# 12_BCKPLN_FPGA_J008340B.net
KiCad netlist of a schematic drawn in EAGLE
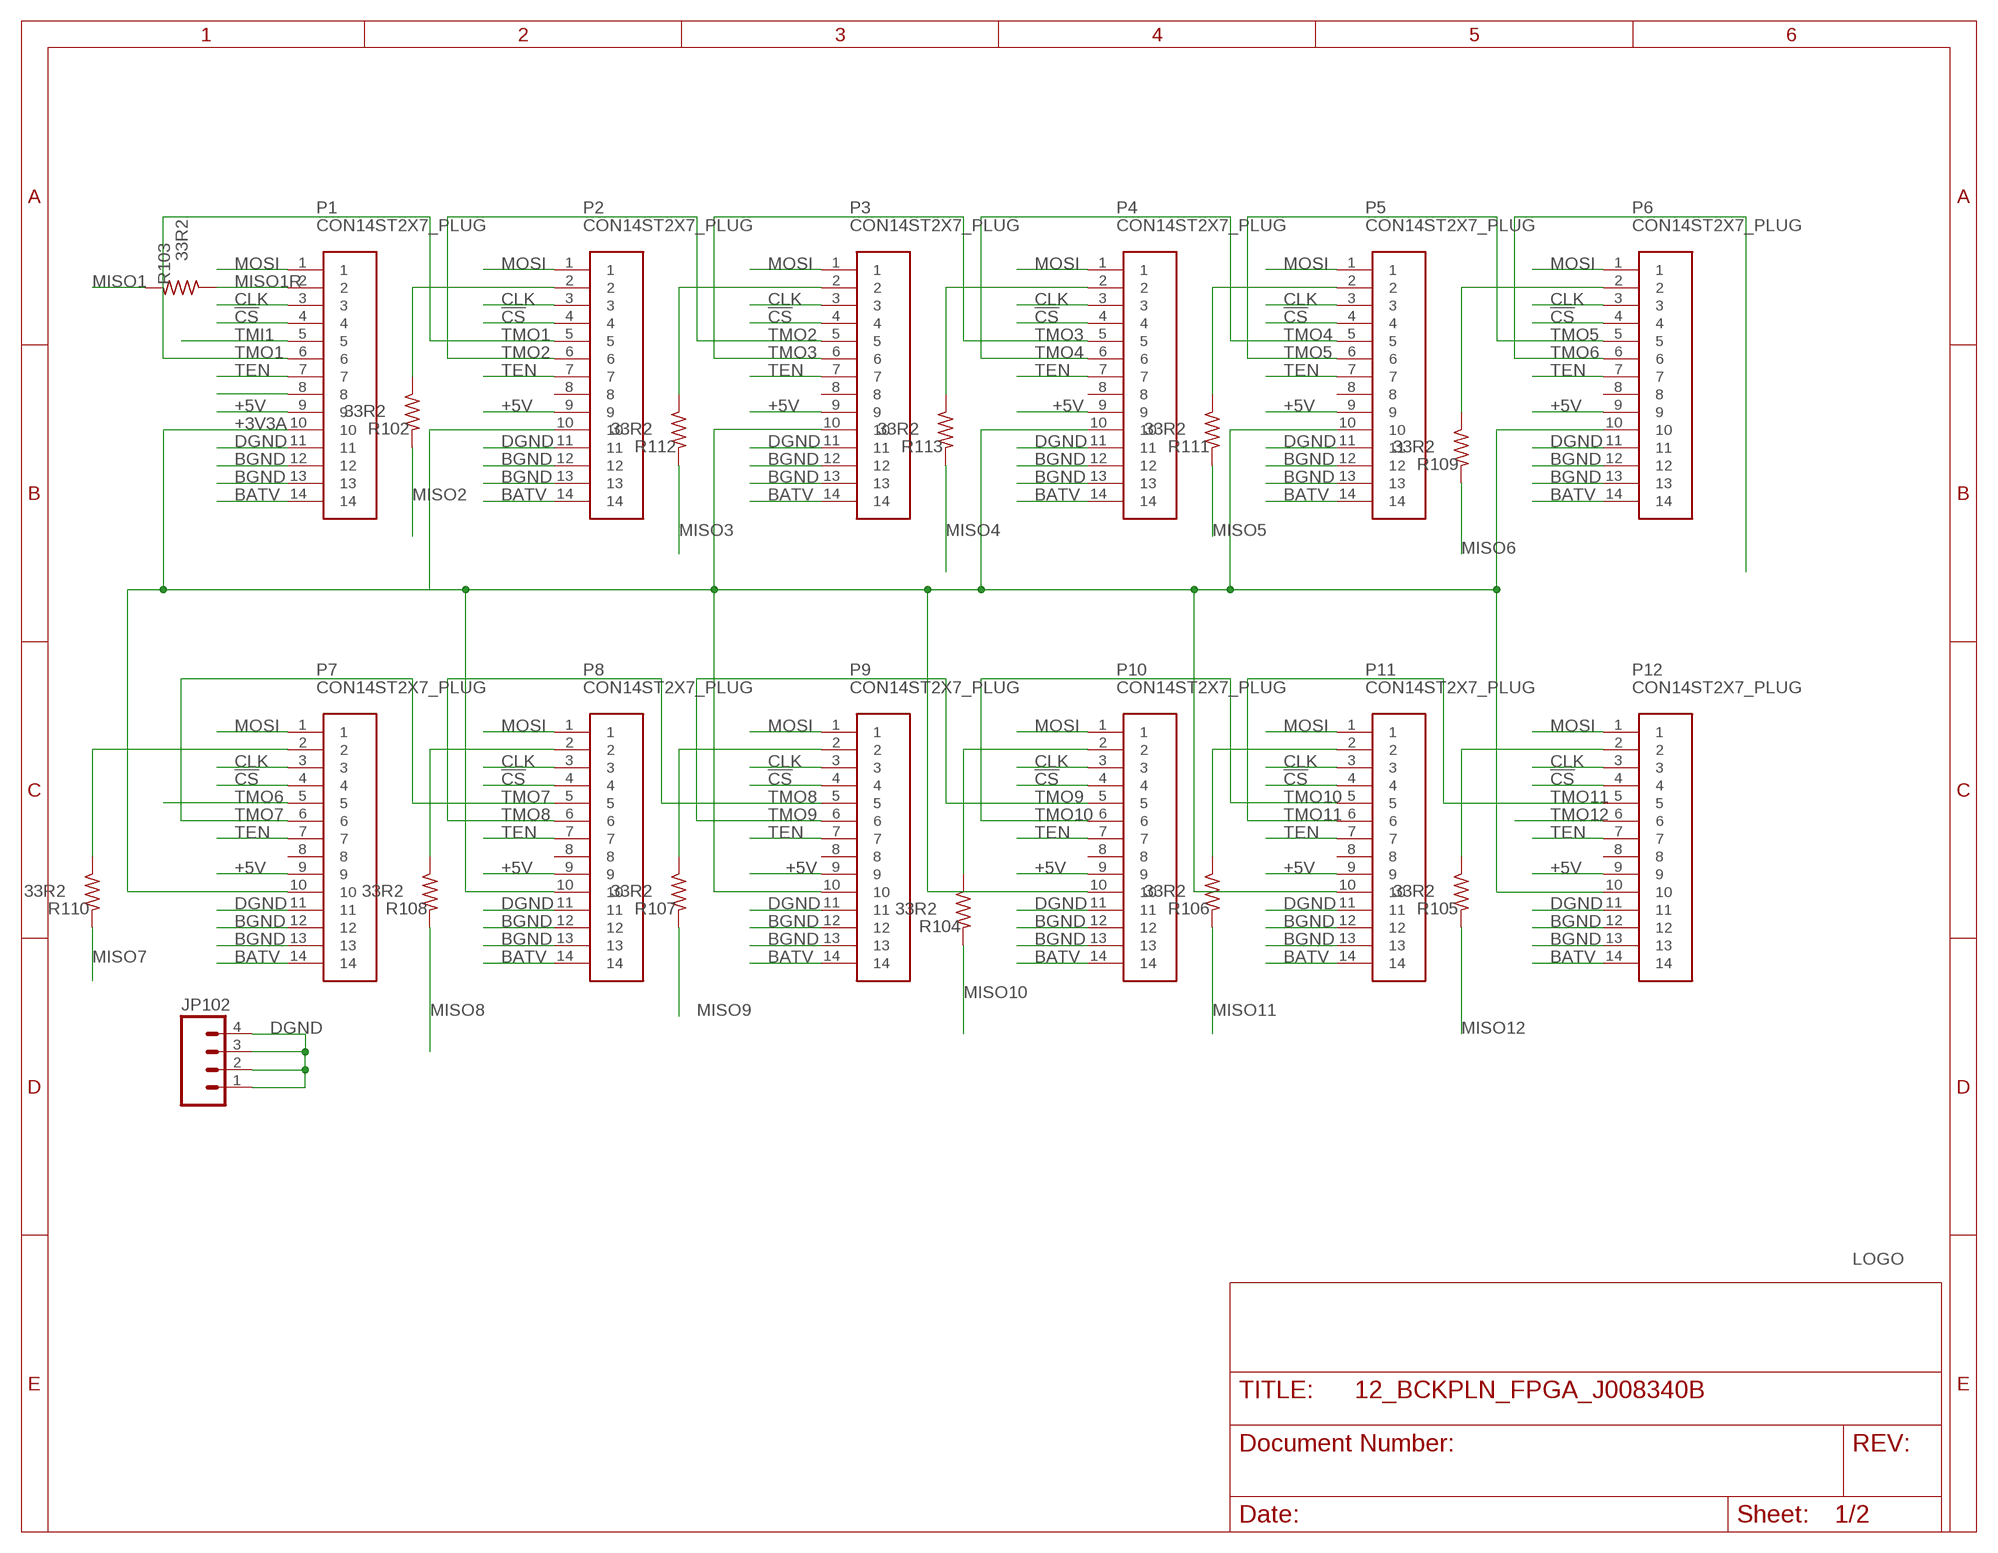
[diagram p0: schematic, sheet 1]
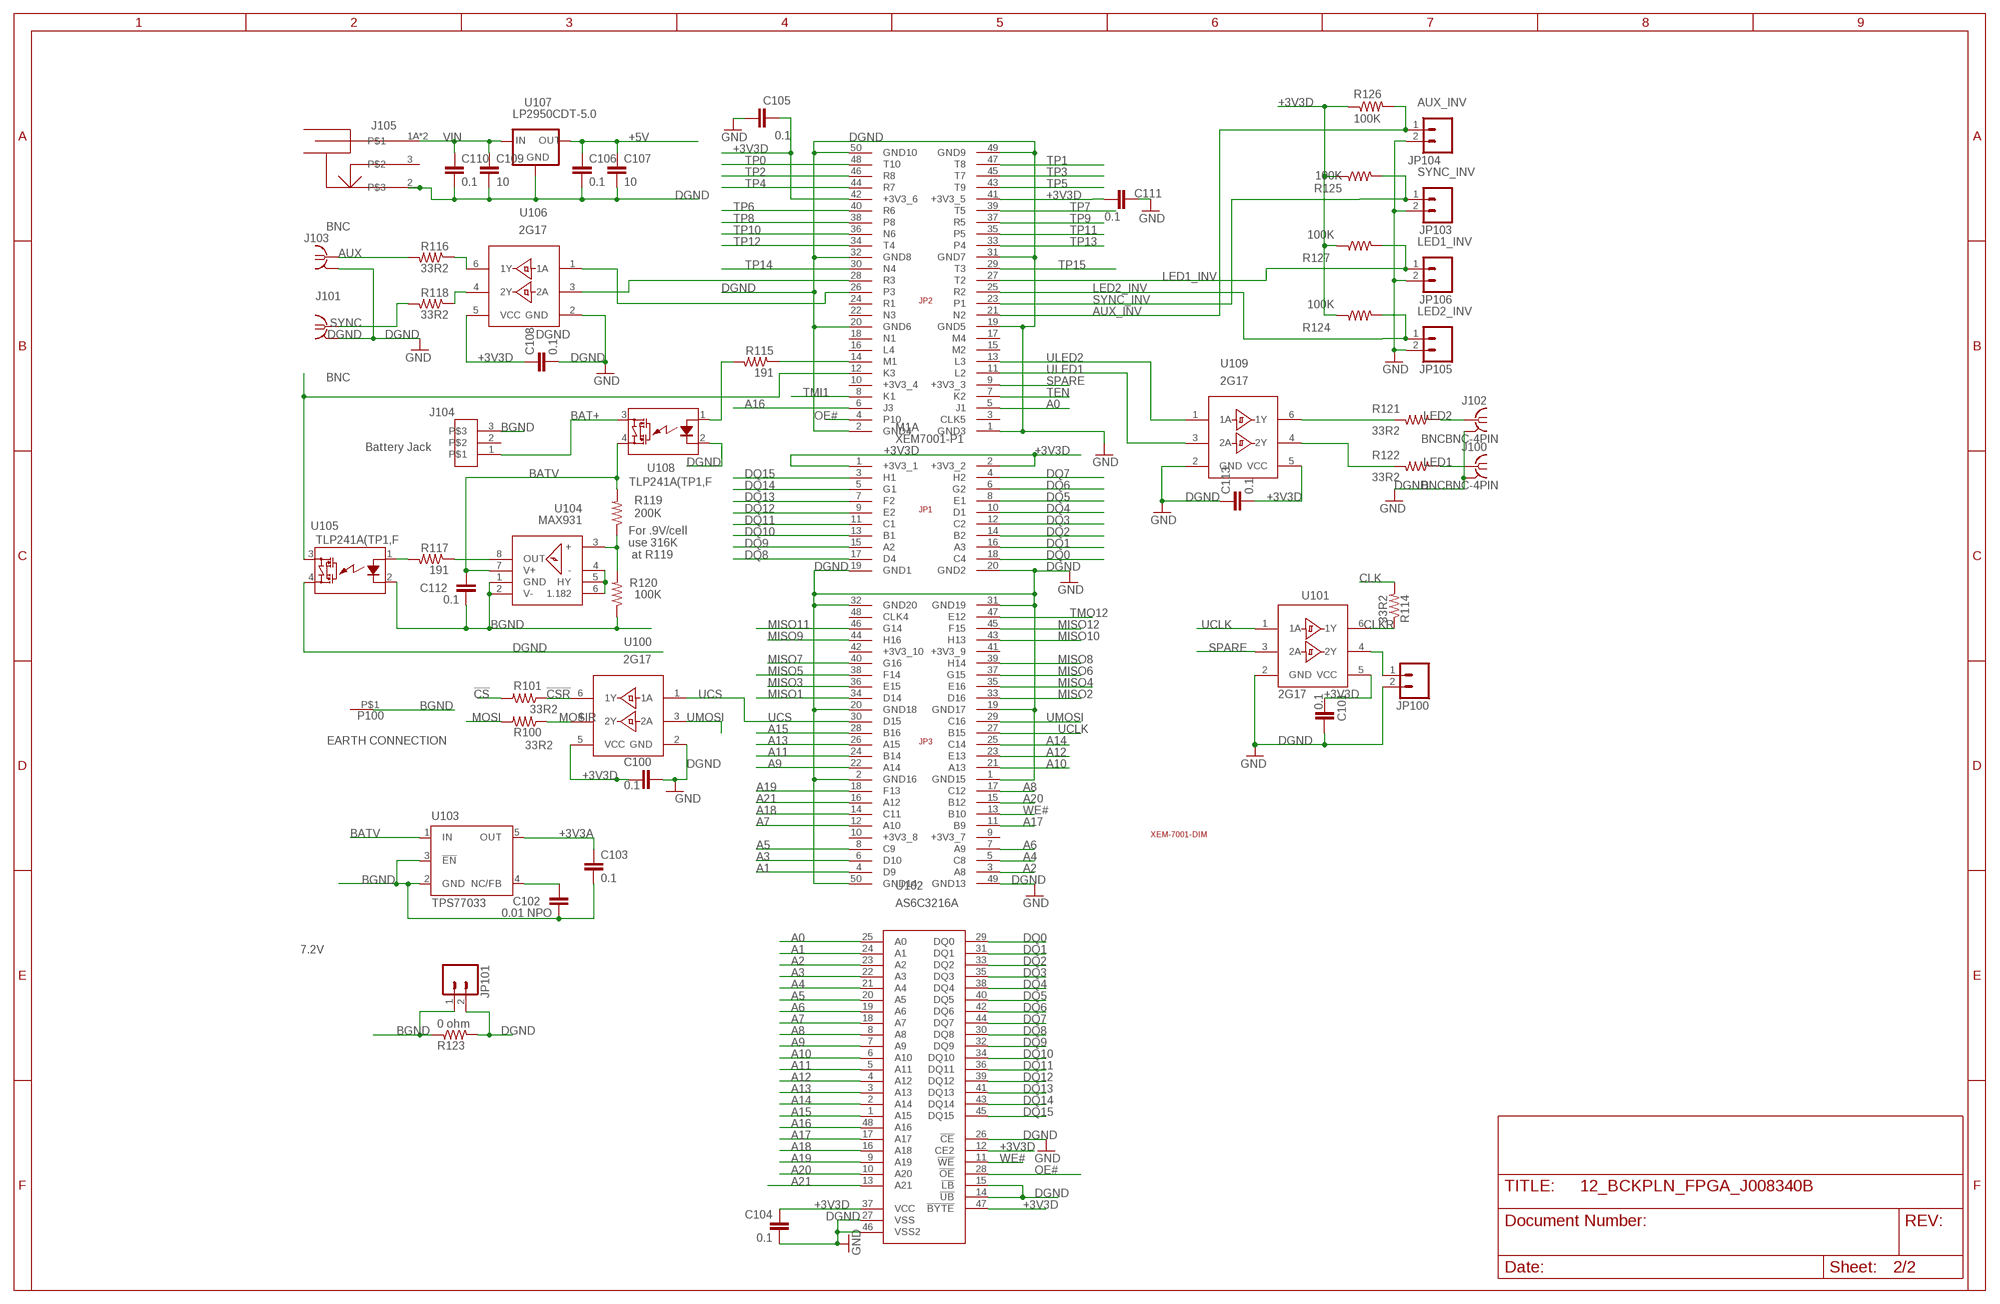
[diagram p1: schematic, sheet 2]

(export (version "E")
  (design (tool "Eeschema 10.0.6"))
  (components
    (comp (ref "JP102")
      (value "M04LOCK")
      (footprint "eagle-import:1X04_LOCK")
      (libsource (lib "eagle-import") (part "M04LOCK"))
    )
    (comp (ref "P1")
      (value "CON14ST2X7_PLUG")
      (footprint "eagle-import:2X7_PLUG")
      (libsource (lib "eagle-import") (part "CON14ST2X7_PLUG"))
    )
    (comp (ref "P2")
      (value "CON14ST2X7_PLUG")
      (footprint "eagle-import:2X7_PLUG")
      (libsource (lib "eagle-import") (part "CON14ST2X7_PLUG"))
    )
    (comp (ref "P3")
      (value "CON14ST2X7_PLUG")
      (footprint "eagle-import:2X7_PLUG")
      (libsource (lib "eagle-import") (part "CON14ST2X7_PLUG"))
    )
    (comp (ref "P4")
      (value "CON14ST2X7_PLUG")
      (footprint "eagle-import:2X7_PLUG")
      (libsource (lib "eagle-import") (part "CON14ST2X7_PLUG"))
    )
    (comp (ref "P5")
      (value "CON14ST2X7_PLUG")
      (footprint "eagle-import:2X7_PLUG")
      (libsource (lib "eagle-import") (part "CON14ST2X7_PLUG"))
    )
    (comp (ref "P6")
      (value "CON14ST2X7_PLUG")
      (footprint "eagle-import:2X7_PLUG")
      (libsource (lib "eagle-import") (part "CON14ST2X7_PLUG"))
    )
    (comp (ref "P7")
      (value "CON14ST2X7_PLUG")
      (footprint "eagle-import:2X7_PLUG")
      (libsource (lib "eagle-import") (part "CON14ST2X7_PLUG"))
    )
    (comp (ref "P8")
      (value "CON14ST2X7_PLUG")
      (footprint "eagle-import:2X7_PLUG")
      (libsource (lib "eagle-import") (part "CON14ST2X7_PLUG"))
    )
    (comp (ref "P9")
      (value "CON14ST2X7_PLUG")
      (footprint "eagle-import:2X7_PLUG")
      (libsource (lib "eagle-import") (part "CON14ST2X7_PLUG"))
    )
    (comp (ref "P10")
      (value "CON14ST2X7_PLUG")
      (footprint "eagle-import:2X7_PLUG")
      (libsource (lib "eagle-import") (part "CON14ST2X7_PLUG"))
    )
    (comp (ref "P11")
      (value "CON14ST2X7_PLUG")
      (footprint "eagle-import:2X7_PLUG")
      (libsource (lib "eagle-import") (part "CON14ST2X7_PLUG"))
    )
    (comp (ref "P12")
      (value "CON14ST2X7_PLUG")
      (footprint "eagle-import:2X7_PLUG")
      (libsource (lib "eagle-import") (part "CON14ST2X7_PLUG"))
    )
    (comp (ref "R102")
      (value "33R2")
      (footprint "eagle-import:0805S")
      (libsource (lib "eagle-import") (part "STEVES_BU_RESISTOR_SM0805S"))
    )
    (comp (ref "R103")
      (value "33R2")
      (footprint "eagle-import:0805S")
      (libsource (lib "eagle-import") (part "STEVES_BU_RESISTOR_SM0805S"))
    )
    (comp (ref "R104")
      (value "33R2")
      (footprint "eagle-import:0805S")
      (libsource (lib "eagle-import") (part "STEVES_BU_RESISTOR_SM0805S"))
    )
    (comp (ref "R105")
      (value "33R2")
      (footprint "eagle-import:0805S")
      (libsource (lib "eagle-import") (part "STEVES_BU_RESISTOR_SM0805S"))
    )
    (comp (ref "R106")
      (value "33R2")
      (footprint "eagle-import:0805S")
      (libsource (lib "eagle-import") (part "STEVES_BU_RESISTOR_SM0805S"))
    )
    (comp (ref "R107")
      (value "33R2")
      (footprint "eagle-import:0805S")
      (libsource (lib "eagle-import") (part "STEVES_BU_RESISTOR_SM0805S"))
    )
    (comp (ref "R108")
      (value "33R2")
      (footprint "eagle-import:0805S")
      (libsource (lib "eagle-import") (part "STEVES_BU_RESISTOR_SM0805S"))
    )
    (comp (ref "R109")
      (value "33R2")
      (footprint "eagle-import:0805S")
      (libsource (lib "eagle-import") (part "STEVES_BU_RESISTOR_SM0805S"))
    )
    (comp (ref "R110")
      (value "33R2")
      (footprint "eagle-import:0805S")
      (libsource (lib "eagle-import") (part "STEVES_BU_RESISTOR_SM0805S"))
    )
    (comp (ref "R111")
      (value "33R2")
      (footprint "eagle-import:0805S")
      (libsource (lib "eagle-import") (part "STEVES_BU_RESISTOR_SM0805S"))
    )
    (comp (ref "R112")
      (value "33R2")
      (footprint "eagle-import:0805S")
      (libsource (lib "eagle-import") (part "STEVES_BU_RESISTOR_SM0805S"))
    )
    (comp (ref "R113")
      (value "33R2")
      (footprint "eagle-import:0805S")
      (libsource (lib "eagle-import") (part "STEVES_BU_RESISTOR_SM0805S"))
    )
    (comp (ref "U$1")
      (value "JFRC-LOGOLOGO_OP")
      (footprint "eagle-import:LOGO_BMP_OP")
      (libsource (lib "eagle-import") (part "JFRC-LOGOLOGO_OP"))
    )
    (comp (ref "C100")
      (value "0.1")
      (footprint "eagle-import:0603S")
      (libsource (lib "eagle-import") (part "CAPS0603S"))
    )
    (comp (ref "C101")
      (value "0.1")
      (footprint "eagle-import:0603S")
      (libsource (lib "eagle-import") (part "CAPS0603S"))
    )
    (comp (ref "C102")
      (value "0.01 NPO")
      (footprint "eagle-import:0805S")
      (libsource (lib "eagle-import") (part "CAPS0805S"))
    )
    (comp (ref "C103")
      (value "0.1")
      (footprint "eagle-import:0603S")
      (libsource (lib "eagle-import") (part "CAPS0603S"))
    )
    (comp (ref "C104")
      (value "0.1")
      (footprint "eagle-import:0603S")
      (libsource (lib "eagle-import") (part "CAPS0603S"))
    )
    (comp (ref "C105")
      (value "0.1")
      (footprint "eagle-import:0603S")
      (libsource (lib "eagle-import") (part "CAPS0603S"))
    )
    (comp (ref "C106")
      (value "0.1")
      (footprint "eagle-import:0603S")
      (libsource (lib "eagle-import") (part "CAPS0603S"))
    )
    (comp (ref "C107")
      (value "10")
      (footprint "eagle-import:1210S")
      (libsource (lib "eagle-import") (part "CAPS1210S"))
    )
    (comp (ref "C108")
      (value "0.1")
      (footprint "eagle-import:0603S")
      (libsource (lib "eagle-import") (part "CAPS0603S"))
    )
    (comp (ref "C109")
      (value "10")
      (footprint "eagle-import:1210S")
      (libsource (lib "eagle-import") (part "CAPS1210S"))
    )
    (comp (ref "C110")
      (value "0.1")
      (footprint "eagle-import:0603S")
      (libsource (lib "eagle-import") (part "CAPS0603S"))
    )
    (comp (ref "C111")
      (value "0.1")
      (footprint "eagle-import:0603S")
      (libsource (lib "eagle-import") (part "CAPS0603S"))
    )
    (comp (ref "C112")
      (value "0.1")
      (footprint "eagle-import:0603S")
      (libsource (lib "eagle-import") (part "CAPS0603S"))
    )
    (comp (ref "C113")
      (value "0.1")
      (footprint "eagle-import:0603S")
      (libsource (lib "eagle-import") (part "CAPS0603S"))
    )
    (comp (ref "J100")
      (value "BNCBNC-4PIN")
      (footprint "eagle-import:BNC-4PIN")
      (libsource (lib "eagle-import") (part "BNCBNC-4PIN"))
    )
    (comp (ref "J101")
      (value "BNC")
      (footprint "eagle-import:BNC-4PIN")
      (libsource (lib "eagle-import") (part "BNCBNC-4PIN"))
    )
    (comp (ref "J102")
      (value "BNCBNC-4PIN")
      (footprint "eagle-import:BNC-4PIN")
      (libsource (lib "eagle-import") (part "BNCBNC-4PIN"))
    )
    (comp (ref "J103")
      (value "BNC")
      (footprint "eagle-import:BNC-4PIN")
      (libsource (lib "eagle-import") (part "BNCBNC-4PIN"))
    )
    (comp (ref "J104")
      (value "Battery Jack")
      (footprint "eagle-import:975")
      (libsource (lib "eagle-import") (part "CON3975"))
    )
    (comp (ref "J105")
      (value "POWER_JACK_SHUNTPJ-002")
      (footprint "eagle-import:PJ-002")
      (libsource (lib "eagle-import") (part "POWER_JACK_SHUNTPJ-002"))
    )
    (comp (ref "JP100")
      (value "M02LOCK")
      (footprint "eagle-import:1X02_LOCK")
      (libsource (lib "eagle-import") (part "M02LOCK"))
    )
    (comp (ref "JP101")
      (value "M02LOCK")
      (footprint "eagle-import:1X02_LOCK")
      (libsource (lib "eagle-import") (part "M02LOCK"))
    )
    (comp (ref "JP103")
      (value "M02LOCK")
      (footprint "eagle-import:1X02_LOCK")
      (libsource (lib "eagle-import") (part "M02LOCK"))
    )
    (comp (ref "JP104")
      (value "M02LOCK")
      (footprint "eagle-import:1X02_LOCK")
      (libsource (lib "eagle-import") (part "M02LOCK"))
    )
    (comp (ref "JP105")
      (value "M02LOCK")
      (footprint "eagle-import:1X02_LOCK")
      (libsource (lib "eagle-import") (part "M02LOCK"))
    )
    (comp (ref "JP106")
      (value "M02LOCK")
      (footprint "eagle-import:1X02_LOCK")
      (libsource (lib "eagle-import") (part "M02LOCK"))
    )
    (comp (ref "M1")
      (value "XEM7001-OUTLINE")
      (footprint "eagle-import:XEM7001-OUTLINE")
      (libsource (lib "eagle-import") (part "XEM7001-OUTLINE"))
    )
    (comp (ref "M1A")
      (value "XEM7001-P1")
      (footprint "eagle-import:2X10")
      (libsource (lib "eagle-import") (part "XEM7001-P1"))
    )
    (comp (ref "M1B")
      (value "XEM7001-P2")
      (footprint "eagle-import:2X25")
      (libsource (lib "eagle-import") (part "XEM7001-P2"))
    )
    (comp (ref "M1C")
      (value "XEM7001-P3")
      (footprint "eagle-import:2X25")
      (libsource (lib "eagle-import") (part "XEM7001-P3"))
    )
    (comp (ref "P100")
      (value "CON1BANANA-1")
      (footprint "eagle-import:BANANA-1")
      (libsource (lib "eagle-import") (part "CON1BANANA-1"))
    )
    (comp (ref "R100")
      (value "33R2")
      (footprint "eagle-import:0805S")
      (libsource (lib "eagle-import") (part "STEVES_BU_RESISTOR_SM0805S"))
    )
    (comp (ref "R101")
      (value "33R2")
      (footprint "eagle-import:0805S")
      (libsource (lib "eagle-import") (part "STEVES_BU_RESISTOR_SM0805S"))
    )
    (comp (ref "R114")
      (value "33R2")
      (footprint "eagle-import:0805S")
      (libsource (lib "eagle-import") (part "STEVES_BU_RESISTOR_SM0805S"))
    )
    (comp (ref "R115")
      (value "191")
      (footprint "eagle-import:0805S")
      (libsource (lib "eagle-import") (part "STEVES_BU_RESISTOR_SM0805S"))
    )
    (comp (ref "R116")
      (value "33R2")
      (footprint "eagle-import:0805S")
      (libsource (lib "eagle-import") (part "RESISTOR_SM0805S"))
    )
    (comp (ref "R117")
      (value "191")
      (footprint "eagle-import:0805S")
      (libsource (lib "eagle-import") (part "STEVES_BU_RESISTOR_SM0805S"))
    )
    (comp (ref "R118")
      (value "33R2")
      (footprint "eagle-import:0805S")
      (libsource (lib "eagle-import") (part "RESISTOR_SM0805S"))
    )
    (comp (ref "R119")
      (value "200K")
      (footprint "eagle-import:0805S")
      (libsource (lib "eagle-import") (part "STEVES_BU_RESISTOR_SM0805S"))
    )
    (comp (ref "R120")
      (value "100K")
      (footprint "eagle-import:0805S")
      (libsource (lib "eagle-import") (part "STEVES_BU_RESISTOR_SM0805S"))
    )
    (comp (ref "R121")
      (value "33R2")
      (footprint "eagle-import:0805S")
      (libsource (lib "eagle-import") (part "RESISTOR_SM0805S"))
    )
    (comp (ref "R122")
      (value "33R2")
      (footprint "eagle-import:0805S")
      (libsource (lib "eagle-import") (part "RESISTOR_SM0805S"))
    )
    (comp (ref "R123")
      (value "0 ohm")
      (footprint "eagle-import:0805S")
      (libsource (lib "eagle-import") (part "STEVES_BU_RESISTOR_SM0805S"))
    )
    (comp (ref "R124")
      (value "100K")
      (footprint "eagle-import:0805S")
      (libsource (lib "eagle-import") (part "STEVES_BU_RESISTOR_SM0805S"))
    )
    (comp (ref "R125")
      (value "100K")
      (footprint "eagle-import:0805S")
      (libsource (lib "eagle-import") (part "STEVES_BU_RESISTOR_SM0805S"))
    )
    (comp (ref "R126")
      (value "100K")
      (footprint "eagle-import:0805S")
      (libsource (lib "eagle-import") (part "STEVES_BU_RESISTOR_SM0805S"))
    )
    (comp (ref "R127")
      (value "100K")
      (footprint "eagle-import:0805S")
      (libsource (lib "eagle-import") (part "STEVES_BU_RESISTOR_SM0805S"))
    )
    (comp (ref "U100")
      (value "2G17")
      (footprint "eagle-import:SOT23-6")
      (libsource (lib "eagle-import") (part "2G17"))
    )
    (comp (ref "U101")
      (value "2G17")
      (footprint "eagle-import:SOT23-6")
      (libsource (lib "eagle-import") (part "2G17"))
    )
    (comp (ref "U102")
      (value "AS6C3216A")
      (footprint "eagle-import:TSSOP48-12X20")
      (libsource (lib "eagle-import") (part "AS6C3216A"))
    )
    (comp (ref "U103")
      (value "TPS77033")
      (footprint "eagle-import:SOT23-DBV")
      (fields (field (name "MF") "TEXAS INSTRUMENTS") (field (name "MPN") "TPS77033DBVT"))
      (libsource (lib "eagle-import") (part "TPS77033"))
    )
    (comp (ref "U104")
      (value "MAX931")
      (footprint "eagle-import:SOIC8")
      (libsource (lib "eagle-import") (part "MAX931"))
    )
    (comp (ref "U105")
      (value "TLP241A(TP1,F")
      (footprint "eagle-import:SMD4-GULL")
      (libsource (lib "eagle-import") (part "RELAY_SSRSMD4-GULL"))
    )
    (comp (ref "U106")
      (value "2G17")
      (footprint "eagle-import:SOT23-6")
      (libsource (lib "eagle-import") (part "2G17"))
    )
    (comp (ref "U107")
      (value "LP2950CDT-5.0")
      (footprint "eagle-import:DPACK")
      (libsource (lib "eagle-import") (part "LP2950?CDT-5.0"))
    )
    (comp (ref "U108")
      (value "TLP241A(TP1,F")
      (footprint "eagle-import:SMD4-GULL")
      (libsource (lib "eagle-import") (part "RELAY_SSRSMD4-GULL"))
    )
    (comp (ref "U109")
      (value "2G17")
      (footprint "eagle-import:SOT23-6")
      (libsource (lib "eagle-import") (part "2G17"))
    )
  )
  (nets
    (net (code "1") (name "+3V3A") (class "Default")
      (node (ref "C103") (pin "1") (pinfunction "1_1") (pintype "passive"))
      (node (ref "P1") (pin "10") (pinfunction "10_10") (pintype "bidirectional"))
      (node (ref "P10") (pin "10") (pinfunction "10_10") (pintype "bidirectional"))
      (node (ref "P11") (pin "10") (pinfunction "10_10") (pintype "bidirectional"))
      (node (ref "P12") (pin "10") (pinfunction "10_10") (pintype "bidirectional"))
      (node (ref "P2") (pin "10") (pinfunction "10_10") (pintype "bidirectional"))
      (node (ref "P3") (pin "10") (pinfunction "10_10") (pintype "bidirectional"))
      (node (ref "P4") (pin "10") (pinfunction "10_10") (pintype "bidirectional"))
      (node (ref "P5") (pin "10") (pinfunction "10_10") (pintype "bidirectional"))
      (node (ref "P6") (pin "10") (pinfunction "10_10") (pintype "bidirectional"))
      (node (ref "P7") (pin "10") (pinfunction "10_10") (pintype "bidirectional"))
      (node (ref "P8") (pin "10") (pinfunction "10_10") (pintype "bidirectional"))
      (node (ref "P9") (pin "10") (pinfunction "10_10") (pintype "bidirectional"))
      (node (ref "U103") (pin "5") (pinfunction "OUT_5") (pintype "passive"))
    )
    (net (code "2") (name "+3V3D") (class "Default")
      (node (ref "C100") (pin "1") (pinfunction "1_1") (pintype "passive"))
      (node (ref "C101") (pin "1") (pinfunction "1_1") (pintype "passive"))
      (node (ref "C104") (pin "1") (pinfunction "1_1") (pintype "passive"))
      (node (ref "C105") (pin "1") (pinfunction "1_1") (pintype "passive"))
      (node (ref "C108") (pin "1") (pinfunction "1_1") (pintype "passive"))
      (node (ref "C111") (pin "1") (pinfunction "1_1") (pintype "passive"))
      (node (ref "C113") (pin "2") (pinfunction "2_2") (pintype "passive"))
      (node (ref "M1A") (pin "1") (pinfunction "+3V3_1_1") (pintype "bidirectional"))
      (node (ref "M1A") (pin "2") (pinfunction "+3V3_2_2") (pintype "bidirectional"))
      (node (ref "M1B") (pin "41") (pinfunction "+3V3_5_41") (pintype "bidirectional"))
      (node (ref "M1B") (pin "42") (pinfunction "+3V3_6_42") (pintype "bidirectional"))
      (node (ref "R124") (pin "1") (pinfunction "1_1") (pintype "passive"))
      (node (ref "R125") (pin "1") (pinfunction "1_1") (pintype "passive"))
      (node (ref "R126") (pin "1") (pinfunction "1_1") (pintype "passive"))
      (node (ref "R127") (pin "1") (pinfunction "1_1") (pintype "passive"))
      (node (ref "U100") (pin "5") (pinfunction "VCC_5") (pintype "bidirectional"))
      (node (ref "U101") (pin "5") (pinfunction "VCC_5") (pintype "bidirectional"))
      (node (ref "U102") (pin "12") (pinfunction "CE2_12") (pintype "bidirectional"))
      (node (ref "U102") (pin "37") (pinfunction "VCC_37") (pintype "bidirectional"))
      (node (ref "U102") (pin "47") (pinfunction "~{BYTE}_47") (pintype "bidirectional"))
      (node (ref "U106") (pin "5") (pinfunction "VCC_5") (pintype "bidirectional"))
      (node (ref "U109") (pin "5") (pinfunction "VCC_5") (pintype "bidirectional"))
    )
    (net (code "3") (name "+5V") (class "Default")
      (node (ref "C106") (pin "1") (pinfunction "1_1") (pintype "passive"))
      (node (ref "C107") (pin "1") (pinfunction "1_1") (pintype "passive"))
      (node (ref "P1") (pin "9") (pinfunction "9_9") (pintype "bidirectional"))
      (node (ref "P10") (pin "9") (pinfunction "9_9") (pintype "bidirectional"))
      (node (ref "P11") (pin "9") (pinfunction "9_9") (pintype "bidirectional"))
      (node (ref "P12") (pin "9") (pinfunction "9_9") (pintype "bidirectional"))
      (node (ref "P2") (pin "9") (pinfunction "9_9") (pintype "bidirectional"))
      (node (ref "P3") (pin "9") (pinfunction "9_9") (pintype "bidirectional"))
      (node (ref "P4") (pin "9") (pinfunction "9_9") (pintype "bidirectional"))
      (node (ref "P5") (pin "9") (pinfunction "9_9") (pintype "bidirectional"))
      (node (ref "P6") (pin "9") (pinfunction "9_9") (pintype "bidirectional"))
      (node (ref "P7") (pin "9") (pinfunction "9_9") (pintype "bidirectional"))
      (node (ref "P8") (pin "9") (pinfunction "9_9") (pintype "bidirectional"))
      (node (ref "P9") (pin "9") (pinfunction "9_9") (pintype "bidirectional"))
      (node (ref "U107") (pin "3") (pinfunction "OUT_3") (pintype "passive"))
    )
    (net (code "4") (name "A0") (class "Default")
      (node (ref "M1B") (pin "5") (pinfunction "J1_5") (pintype "bidirectional"))
      (node (ref "U102") (pin "25") (pinfunction "A0_25") (pintype "bidirectional"))
    )
    (net (code "5") (name "A1") (class "Default")
      (node (ref "M1C") (pin "4") (pinfunction "D9_4") (pintype "bidirectional"))
      (node (ref "U102") (pin "24") (pinfunction "A1_24") (pintype "bidirectional"))
    )
    (net (code "6") (name "A2") (class "Default")
      (node (ref "M1C") (pin "3") (pinfunction "A8_3") (pintype "bidirectional"))
      (node (ref "U102") (pin "23") (pinfunction "A2_23") (pintype "bidirectional"))
    )
    (net (code "7") (name "A3") (class "Default")
      (node (ref "M1C") (pin "6") (pinfunction "D10_6") (pintype "bidirectional"))
      (node (ref "U102") (pin "22") (pinfunction "A3_22") (pintype "bidirectional"))
    )
    (net (code "8") (name "A4") (class "Default")
      (node (ref "M1C") (pin "5") (pinfunction "C8_5") (pintype "bidirectional"))
      (node (ref "U102") (pin "21") (pinfunction "A4_21") (pintype "bidirectional"))
    )
    (net (code "9") (name "A5") (class "Default")
      (node (ref "M1C") (pin "8") (pinfunction "C9_8") (pintype "bidirectional"))
      (node (ref "U102") (pin "20") (pinfunction "A5_20") (pintype "bidirectional"))
    )
    (net (code "10") (name "A6") (class "Default")
      (node (ref "M1C") (pin "7") (pinfunction "A9_7") (pintype "bidirectional"))
      (node (ref "U102") (pin "19") (pinfunction "A6_19") (pintype "bidirectional"))
    )
    (net (code "11") (name "A7") (class "Default")
      (node (ref "M1C") (pin "12") (pinfunction "A10_12") (pintype "bidirectional"))
      (node (ref "U102") (pin "18") (pinfunction "A7_18") (pintype "bidirectional"))
    )
    (net (code "12") (name "A8") (class "Default")
      (node (ref "M1C") (pin "17") (pinfunction "C12_17") (pintype "bidirectional"))
      (node (ref "U102") (pin "8") (pinfunction "A8_8") (pintype "bidirectional"))
    )
    (net (code "13") (name "A9") (class "Default")
      (node (ref "M1C") (pin "22") (pinfunction "A14_22") (pintype "bidirectional"))
      (node (ref "U102") (pin "7") (pinfunction "A9_7") (pintype "bidirectional"))
    )
    (net (code "14") (name "A10") (class "Default")
      (node (ref "M1C") (pin "21") (pinfunction "A13_21") (pintype "bidirectional"))
      (node (ref "U102") (pin "6") (pinfunction "A10_6") (pintype "bidirectional"))
    )
    (net (code "15") (name "A11") (class "Default")
      (node (ref "M1C") (pin "24") (pinfunction "B14_24") (pintype "bidirectional"))
      (node (ref "U102") (pin "5") (pinfunction "A11_5") (pintype "bidirectional"))
    )
    (net (code "16") (name "A12") (class "Default")
      (node (ref "M1C") (pin "23") (pinfunction "E13_23") (pintype "bidirectional"))
      (node (ref "U102") (pin "4") (pinfunction "A12_4") (pintype "bidirectional"))
    )
    (net (code "17") (name "A13") (class "Default")
      (node (ref "M1C") (pin "26") (pinfunction "A15_26") (pintype "bidirectional"))
      (node (ref "U102") (pin "3") (pinfunction "A13_3") (pintype "bidirectional"))
    )
    (net (code "18") (name "A14") (class "Default")
      (node (ref "M1C") (pin "25") (pinfunction "C14_25") (pintype "bidirectional"))
      (node (ref "U102") (pin "2") (pinfunction "A14_2") (pintype "bidirectional"))
    )
    (net (code "19") (name "A15") (class "Default")
      (node (ref "M1C") (pin "28") (pinfunction "B16_28") (pintype "bidirectional"))
      (node (ref "U102") (pin "1") (pinfunction "A15_1") (pintype "bidirectional"))
    )
    (net (code "20") (name "A16") (class "Default")
      (node (ref "M1B") (pin "6") (pinfunction "J3_6") (pintype "bidirectional"))
      (node (ref "U102") (pin "48") (pinfunction "A16_48") (pintype "bidirectional"))
    )
    (net (code "21") (name "A17") (class "Default")
      (node (ref "M1C") (pin "11") (pinfunction "B9_11") (pintype "bidirectional"))
      (node (ref "U102") (pin "17") (pinfunction "A17_17") (pintype "bidirectional"))
    )
    (net (code "22") (name "A18") (class "Default")
      (node (ref "M1C") (pin "14") (pinfunction "C11_14") (pintype "bidirectional"))
      (node (ref "U102") (pin "16") (pinfunction "A18_16") (pintype "bidirectional"))
    )
    (net (code "23") (name "A19") (class "Default")
      (node (ref "M1C") (pin "18") (pinfunction "F13_18") (pintype "bidirectional"))
      (node (ref "U102") (pin "9") (pinfunction "A19_9") (pintype "bidirectional"))
    )
    (net (code "24") (name "A20") (class "Default")
      (node (ref "M1C") (pin "15") (pinfunction "B12_15") (pintype "bidirectional"))
      (node (ref "U102") (pin "10") (pinfunction "A20_10") (pintype "bidirectional"))
    )
    (net (code "25") (name "A21") (class "Default")
      (node (ref "M1C") (pin "16") (pinfunction "A12_16") (pintype "bidirectional"))
      (node (ref "U102") (pin "13") (pinfunction "A21_13") (pintype "bidirectional"))
    )
    (net (code "26") (name "AUX") (class "Default")
      (node (ref "J103") (pin "S") (pinfunction "1_S") (pintype "passive"))
      (node (ref "R116") (pin "2") (pinfunction "2_2") (pintype "passive"))
    )
    (net (code "27") (name "AUX_INV") (class "Default")
      (node (ref "JP104") (pin "1") (pinfunction "1_1") (pintype "passive"))
      (node (ref "M1B") (pin "21") (pinfunction "N2_21") (pintype "bidirectional"))
      (node (ref "R126") (pin "2") (pinfunction "2_2") (pintype "passive"))
    )
    (net (code "28") (name "BAT+") (class "Default")
      (node (ref "J104") (pin "1") (pinfunction "P$1_1") (pintype "bidirectional"))
      (node (ref "U108") (pin "3") (pinfunction "DS1_3") (pintype "passive"))
    )
    (net (code "29") (name "BATV") (class "Default")
      (node (ref "C112") (pin "1") (pinfunction "1_1") (pintype "passive"))
      (node (ref "P1") (pin "14") (pinfunction "14_14") (pintype "bidirectional"))
      (node (ref "P10") (pin "14") (pinfunction "14_14") (pintype "bidirectional"))
      (node (ref "P11") (pin "14") (pinfunction "14_14") (pintype "bidirectional"))
      (node (ref "P12") (pin "14") (pinfunction "14_14") (pintype "bidirectional"))
      (node (ref "P2") (pin "14") (pinfunction "14_14") (pintype "bidirectional"))
      (node (ref "P3") (pin "14") (pinfunction "14_14") (pintype "bidirectional"))
      (node (ref "P4") (pin "14") (pinfunction "14_14") (pintype "bidirectional"))
      (node (ref "P5") (pin "14") (pinfunction "14_14") (pintype "bidirectional"))
      (node (ref "P6") (pin "14") (pinfunction "14_14") (pintype "bidirectional"))
      (node (ref "P7") (pin "14") (pinfunction "14_14") (pintype "bidirectional"))
      (node (ref "P8") (pin "14") (pinfunction "14_14") (pintype "bidirectional"))
      (node (ref "P9") (pin "14") (pinfunction "14_14") (pintype "bidirectional"))
      (node (ref "R119") (pin "2") (pinfunction "2_2") (pintype "passive"))
      (node (ref "U103") (pin "1") (pinfunction "IN_1") (pintype "input"))
      (node (ref "U104") (pin "7") (pinfunction "V+_7") (pintype "bidirectional"))
      (node (ref "U108") (pin "4") (pinfunction "DS2_4") (pintype "passive"))
    )
    (net (code "30") (name "BGND") (class "Default")
      (node (ref "C102") (pin "2") (pinfunction "2_2") (pintype "passive"))
      (node (ref "C103") (pin "2") (pinfunction "2_2") (pintype "passive"))
      (node (ref "C112") (pin "2") (pinfunction "2_2") (pintype "passive"))
      (node (ref "J104") (pin "3") (pinfunction "P$3_3") (pintype "bidirectional"))
      (node (ref "JP101") (pin "1") (pinfunction "1_1") (pintype "passive"))
      (node (ref "P1") (pin "12") (pinfunction "12_12") (pintype "bidirectional"))
      (node (ref "P1") (pin "13") (pinfunction "13_13") (pintype "bidirectional"))
      (node (ref "P10") (pin "12") (pinfunction "12_12") (pintype "bidirectional"))
      (node (ref "P10") (pin "13") (pinfunction "13_13") (pintype "bidirectional"))
      (node (ref "P100") (pin "P$1") (pinfunction "1_P$1") (pintype "bidirectional"))
      (node (ref "P11") (pin "12") (pinfunction "12_12") (pintype "bidirectional"))
      (node (ref "P11") (pin "13") (pinfunction "13_13") (pintype "bidirectional"))
      (node (ref "P12") (pin "12") (pinfunction "12_12") (pintype "bidirectional"))
      (node (ref "P12") (pin "13") (pinfunction "13_13") (pintype "bidirectional"))
      (node (ref "P2") (pin "12") (pinfunction "12_12") (pintype "bidirectional"))
      (node (ref "P2") (pin "13") (pinfunction "13_13") (pintype "bidirectional"))
      (node (ref "P3") (pin "12") (pinfunction "12_12") (pintype "bidirectional"))
      (node (ref "P3") (pin "13") (pinfunction "13_13") (pintype "bidirectional"))
      (node (ref "P4") (pin "12") (pinfunction "12_12") (pintype "bidirectional"))
      (node (ref "P4") (pin "13") (pinfunction "13_13") (pintype "bidirectional"))
      (node (ref "P5") (pin "12") (pinfunction "12_12") (pintype "bidirectional"))
      (node (ref "P5") (pin "13") (pinfunction "13_13") (pintype "bidirectional"))
      (node (ref "P6") (pin "12") (pinfunction "12_12") (pintype "bidirectional"))
      (node (ref "P6") (pin "13") (pinfunction "13_13") (pintype "bidirectional"))
      (node (ref "P7") (pin "12") (pinfunction "12_12") (pintype "bidirectional"))
      (node (ref "P7") (pin "13") (pinfunction "13_13") (pintype "bidirectional"))
      (node (ref "P8") (pin "12") (pinfunction "12_12") (pintype "bidirectional"))
      (node (ref "P8") (pin "13") (pinfunction "13_13") (pintype "bidirectional"))
      (node (ref "P9") (pin "12") (pinfunction "12_12") (pintype "bidirectional"))
      (node (ref "P9") (pin "13") (pinfunction "13_13") (pintype "bidirectional"))
      (node (ref "R120") (pin "1") (pinfunction "1_1") (pintype "passive"))
      (node (ref "R123") (pin "1") (pinfunction "1_1") (pintype "passive"))
      (node (ref "U103") (pin "2") (pinfunction "GND_2") (pintype "power_in"))
      (node (ref "U103") (pin "3") (pinfunction "~{EN}_3") (pintype "input"))
      (node (ref "U104") (pin "1") (pinfunction "GND_1") (pintype "bidirectional"))
      (node (ref "U104") (pin "2") (pinfunction "V-_2") (pintype "bidirectional"))
      (node (ref "U105") (pin "2") (pinfunction "K_2") (pintype "passive"))
    )
    (net (code "31") (name "CLK") (class "Default")
      (node (ref "P1") (pin "3") (pinfunction "3_3") (pintype "bidirectional"))
      (node (ref "P10") (pin "3") (pinfunction "3_3") (pintype "bidirectional"))
      (node (ref "P11") (pin "3") (pinfunction "3_3") (pintype "bidirectional"))
      (node (ref "P12") (pin "3") (pinfunction "3_3") (pintype "bidirectional"))
      (node (ref "P2") (pin "3") (pinfunction "3_3") (pintype "bidirectional"))
      (node (ref "P3") (pin "3") (pinfunction "3_3") (pintype "bidirectional"))
      (node (ref "P4") (pin "3") (pinfunction "3_3") (pintype "bidirectional"))
      (node (ref "P5") (pin "3") (pinfunction "3_3") (pintype "bidirectional"))
      (node (ref "P6") (pin "3") (pinfunction "3_3") (pintype "bidirectional"))
      (node (ref "P7") (pin "3") (pinfunction "3_3") (pintype "bidirectional"))
      (node (ref "P8") (pin "3") (pinfunction "3_3") (pintype "bidirectional"))
      (node (ref "P9") (pin "3") (pinfunction "3_3") (pintype "bidirectional"))
      (node (ref "R114") (pin "2") (pinfunction "2_2") (pintype "passive"))
    )
    (net (code "32") (name "CLKR") (class "Default")
      (node (ref "R114") (pin "1") (pinfunction "1_1") (pintype "passive"))
      (node (ref "U101") (pin "6") (pinfunction "1Y_6") (pintype "bidirectional"))
    )
    (net (code "33") (name "DGND") (class "Default")
      (node (ref "C100") (pin "2") (pinfunction "2_2") (pintype "passive"))
      (node (ref "C101") (pin "2") (pinfunction "2_2") (pintype "passive"))
      (node (ref "C104") (pin "2") (pinfunction "2_2") (pintype "passive"))
      (node (ref "C105") (pin "2") (pinfunction "2_2") (pintype "passive"))
      (node (ref "C106") (pin "2") (pinfunction "2_2") (pintype "passive"))
      (node (ref "C107") (pin "2") (pinfunction "2_2") (pintype "passive"))
      (node (ref "C108") (pin "2") (pinfunction "2_2") (pintype "passive"))
      (node (ref "C109") (pin "2") (pinfunction "2_2") (pintype "passive"))
      (node (ref "C110") (pin "2") (pinfunction "2_2") (pintype "passive"))
      (node (ref "C111") (pin "2") (pinfunction "2_2") (pintype "passive"))
      (node (ref "C113") (pin "1") (pinfunction "1_1") (pintype "passive"))
      (node (ref "J100") (pin "G1") (pinfunction "GND_G1") (pintype "passive"))
      (node (ref "J100") (pin "G2") (pinfunction "GND_G2") (pintype "passive"))
      (node (ref "J100") (pin "G3") (pinfunction "GND_G3") (pintype "passive"))
      (node (ref "J100") (pin "G4") (pinfunction "GND_G4") (pintype "passive"))
      (node (ref "J101") (pin "G1") (pinfunction "GND_G1") (pintype "passive"))
      (node (ref "J101") (pin "G2") (pinfunction "GND_G2") (pintype "passive"))
      (node (ref "J101") (pin "G3") (pinfunction "GND_G3") (pintype "passive"))
      (node (ref "J101") (pin "G4") (pinfunction "GND_G4") (pintype "passive"))
      (node (ref "J102") (pin "G1") (pinfunction "GND_G1") (pintype "passive"))
      (node (ref "J102") (pin "G2") (pinfunction "GND_G2") (pintype "passive"))
      (node (ref "J102") (pin "G3") (pinfunction "GND_G3") (pintype "passive"))
      (node (ref "J102") (pin "G4") (pinfunction "GND_G4") (pintype "passive"))
      (node (ref "J103") (pin "G1") (pinfunction "GND_G1") (pintype "passive"))
      (node (ref "J103") (pin "G2") (pinfunction "GND_G2") (pintype "passive"))
      (node (ref "J103") (pin "G3") (pinfunction "GND_G3") (pintype "passive"))
      (node (ref "J103") (pin "G4") (pinfunction "GND_G4") (pintype "passive"))
      (node (ref "J105") (pin "2") (pinfunction "P$3_2") (pintype "bidirectional"))
      (node (ref "JP100") (pin "2") (pinfunction "2_2") (pintype "passive"))
      (node (ref "JP101") (pin "2") (pinfunction "2_2") (pintype "passive"))
      (node (ref "JP102") (pin "1") (pinfunction "1_1") (pintype "passive"))
      (node (ref "JP102") (pin "2") (pinfunction "2_2") (pintype "passive"))
      (node (ref "JP102") (pin "3") (pinfunction "3_3") (pintype "passive"))
      (node (ref "JP102") (pin "4") (pinfunction "4_4") (pintype "passive"))
      (node (ref "JP103") (pin "2") (pinfunction "2_2") (pintype "passive"))
      (node (ref "JP104") (pin "2") (pinfunction "2_2") (pintype "passive"))
      (node (ref "JP105") (pin "2") (pinfunction "2_2") (pintype "passive"))
      (node (ref "JP106") (pin "2") (pinfunction "2_2") (pintype "passive"))
      (node (ref "M1A") (pin "19") (pinfunction "GND1_19") (pintype "bidirectional"))
      (node (ref "M1A") (pin "20") (pinfunction "GND2_20") (pintype "bidirectional"))
      (node (ref "M1B") (pin "1") (pinfunction "GND3_1") (pintype "bidirectional"))
      (node (ref "M1B") (pin "19") (pinfunction "GND5_19") (pintype "bidirectional"))
      (node (ref "M1B") (pin "2") (pinfunction "GND4_2") (pintype "bidirectional"))
      (node (ref "M1B") (pin "20") (pinfunction "GND6_20") (pintype "bidirectional"))
      (node (ref "M1B") (pin "31") (pinfunction "GND7_31") (pintype "bidirectional"))
      (node (ref "M1B") (pin "32") (pinfunction "GND8_32") (pintype "bidirectional"))
      (node (ref "M1B") (pin "49") (pinfunction "GND9_49") (pintype "bidirectional"))
      (node (ref "M1B") (pin "50") (pinfunction "GND10_50") (pintype "bidirectional"))
      (node (ref "M1C") (pin "1") (pinfunction "GND15_1") (pintype "bidirectional"))
      (node (ref "M1C") (pin "19") (pinfunction "GND17_19") (pintype "bidirectional"))
      (node (ref "M1C") (pin "2") (pinfunction "GND16_2") (pintype "bidirectional"))
      (node (ref "M1C") (pin "20") (pinfunction "GND18_20") (pintype "bidirectional"))
      (node (ref "M1C") (pin "31") (pinfunction "GND19_31") (pintype "bidirectional"))
      (node (ref "M1C") (pin "32") (pinfunction "GND20_32") (pintype "bidirectional"))
      (node (ref "M1C") (pin "49") (pinfunction "GND13_49") (pintype "bidirectional"))
      (node (ref "M1C") (pin "50") (pinfunction "GND14_50") (pintype "bidirectional"))
      (node (ref "P1") (pin "11") (pinfunction "11_11") (pintype "bidirectional"))
      (node (ref "P10") (pin "11") (pinfunction "11_11") (pintype "bidirectional"))
      (node (ref "P11") (pin "11") (pinfunction "11_11") (pintype "bidirectional"))
      (node (ref "P12") (pin "11") (pinfunction "11_11") (pintype "bidirectional"))
      (node (ref "P2") (pin "11") (pinfunction "11_11") (pintype "bidirectional"))
      (node (ref "P3") (pin "11") (pinfunction "11_11") (pintype "bidirectional"))
      (node (ref "P4") (pin "11") (pinfunction "11_11") (pintype "bidirectional"))
      (node (ref "P5") (pin "11") (pinfunction "11_11") (pintype "bidirectional"))
      (node (ref "P6") (pin "11") (pinfunction "11_11") (pintype "bidirectional"))
      (node (ref "P7") (pin "11") (pinfunction "11_11") (pintype "bidirectional"))
      (node (ref "P8") (pin "11") (pinfunction "11_11") (pintype "bidirectional"))
      (node (ref "P9") (pin "11") (pinfunction "11_11") (pintype "bidirectional"))
      (node (ref "R123") (pin "2") (pinfunction "2_2") (pintype "passive"))
      (node (ref "U100") (pin "2") (pinfunction "GND_2") (pintype "bidirectional"))
      (node (ref "U101") (pin "2") (pinfunction "GND_2") (pintype "bidirectional"))
      (node (ref "U102") (pin "14") (pinfunction "~{UB}_14") (pintype "bidirectional"))
      (node (ref "U102") (pin "15") (pinfunction "~{LB}_15") (pintype "bidirectional"))
      (node (ref "U102") (pin "26") (pinfunction "~{CE}_26") (pintype "bidirectional"))
      (node (ref "U102") (pin "27") (pinfunction "VSS_27") (pintype "bidirectional"))
      (node (ref "U102") (pin "46") (pinfunction "VSS2_46") (pintype "bidirectional"))
      (node (ref "U105") (pin "4") (pinfunction "DS2_4") (pintype "passive"))
      (node (ref "U106") (pin "2") (pinfunction "GND_2") (pintype "bidirectional"))
      (node (ref "U107") (pin "4") (pinfunction "GND_4") (pintype "input"))
      (node (ref "U108") (pin "2") (pinfunction "K_2") (pintype "passive"))
      (node (ref "U109") (pin "2") (pinfunction "GND_2") (pintype "bidirectional"))
    )
    (net (code "34") (name "DQ0") (class "Default")
      (node (ref "M1A") (pin "18") (pinfunction "C4_18") (pintype "bidirectional"))
      (node (ref "U102") (pin "29") (pinfunction "DQ0_29") (pintype "bidirectional"))
    )
    (net (code "35") (name "DQ1") (class "Default")
      (node (ref "M1A") (pin "16") (pinfunction "A3_16") (pintype "bidirectional"))
      (node (ref "U102") (pin "31") (pinfunction "DQ1_31") (pintype "bidirectional"))
    )
    (net (code "36") (name "DQ2") (class "Default")
      (node (ref "M1A") (pin "14") (pinfunction "B2_14") (pintype "bidirectional"))
      (node (ref "U102") (pin "33") (pinfunction "DQ2_33") (pintype "bidirectional"))
    )
    (net (code "37") (name "DQ3") (class "Default")
      (node (ref "M1A") (pin "12") (pinfunction "C2_12") (pintype "bidirectional"))
      (node (ref "U102") (pin "35") (pinfunction "DQ3_35") (pintype "bidirectional"))
    )
    (net (code "38") (name "DQ4") (class "Default")
      (node (ref "M1A") (pin "10") (pinfunction "D1_10") (pintype "bidirectional"))
      (node (ref "U102") (pin "38") (pinfunction "DQ4_38") (pintype "bidirectional"))
    )
    (net (code "39") (name "DQ5") (class "Default")
      (node (ref "M1A") (pin "8") (pinfunction "E1_8") (pintype "bidirectional"))
      (node (ref "U102") (pin "40") (pinfunction "DQ5_40") (pintype "bidirectional"))
    )
    (net (code "40") (name "DQ6") (class "Default")
      (node (ref "M1A") (pin "6") (pinfunction "G2_6") (pintype "bidirectional"))
      (node (ref "U102") (pin "42") (pinfunction "DQ6_42") (pintype "bidirectional"))
    )
    (net (code "41") (name "DQ7") (class "Default")
      (node (ref "M1A") (pin "4") (pinfunction "H2_4") (pintype "bidirectional"))
      (node (ref "U102") (pin "44") (pinfunction "DQ7_44") (pintype "bidirectional"))
    )
    (net (code "42") (name "DQ8") (class "Default")
      (node (ref "M1A") (pin "17") (pinfunction "D4_17") (pintype "bidirectional"))
      (node (ref "U102") (pin "30") (pinfunction "DQ8_30") (pintype "bidirectional"))
    )
    (net (code "43") (name "DQ9") (class "Default")
      (node (ref "M1A") (pin "15") (pinfunction "A2_15") (pintype "bidirectional"))
      (node (ref "U102") (pin "32") (pinfunction "DQ9_32") (pintype "bidirectional"))
    )
    (net (code "44") (name "DQ10") (class "Default")
      (node (ref "M1A") (pin "13") (pinfunction "B1_13") (pintype "bidirectional"))
      (node (ref "U102") (pin "34") (pinfunction "DQ10_34") (pintype "bidirectional"))
    )
    (net (code "45") (name "DQ11") (class "Default")
      (node (ref "M1A") (pin "11") (pinfunction "C1_11") (pintype "bidirectional"))
      (node (ref "U102") (pin "36") (pinfunction "DQ11_36") (pintype "bidirectional"))
    )
    (net (code "46") (name "DQ12") (class "Default")
      (node (ref "M1A") (pin "9") (pinfunction "E2_9") (pintype "bidirectional"))
      (node (ref "U102") (pin "39") (pinfunction "DQ12_39") (pintype "bidirectional"))
    )
    (net (code "47") (name "DQ13") (class "Default")
      (node (ref "M1A") (pin "7") (pinfunction "F2_7") (pintype "bidirectional"))
      (node (ref "U102") (pin "41") (pinfunction "DQ13_41") (pintype "bidirectional"))
    )
    (net (code "48") (name "DQ14") (class "Default")
      (node (ref "M1A") (pin "5") (pinfunction "G1_5") (pintype "bidirectional"))
      (node (ref "U102") (pin "43") (pinfunction "DQ14_43") (pintype "bidirectional"))
    )
    (net (code "49") (name "DQ15") (class "Default")
      (node (ref "M1A") (pin "3") (pinfunction "H1_3") (pintype "bidirectional"))
      (node (ref "U102") (pin "45") (pinfunction "DQ15_45") (pintype "bidirectional"))
    )
    (net (code "50") (name "LED1") (class "Default")
      (node (ref "J100") (pin "S") (pinfunction "1_S") (pintype "passive"))
      (node (ref "R122") (pin "1") (pinfunction "1_1") (pintype "passive"))
    )
    (net (code "51") (name "LED1_INV") (class "Default")
      (node (ref "JP106") (pin "1") (pinfunction "1_1") (pintype "passive"))
      (node (ref "M1B") (pin "27") (pinfunction "T2_27") (pintype "bidirectional"))
      (node (ref "R127") (pin "2") (pinfunction "2_2") (pintype "passive"))
    )
    (net (code "52") (name "LED2") (class "Default")
      (node (ref "J102") (pin "S") (pinfunction "1_S") (pintype "passive"))
      (node (ref "R121") (pin "1") (pinfunction "1_1") (pintype "passive"))
    )
    (net (code "53") (name "LED2_INV") (class "Default")
      (node (ref "JP105") (pin "1") (pinfunction "1_1") (pintype "passive"))
      (node (ref "M1B") (pin "25") (pinfunction "R2_25") (pintype "bidirectional"))
      (node (ref "R124") (pin "2") (pinfunction "2_2") (pintype "passive"))
    )
    (net (code "54") (name "MISO1") (class "Default")
      (node (ref "M1C") (pin "34") (pinfunction "D14_34") (pintype "bidirectional"))
      (node (ref "R103") (pin "2") (pinfunction "2_2") (pintype "passive"))
    )
    (net (code "55") (name "MISO1R") (class "Default")
      (node (ref "P1") (pin "2") (pinfunction "2_2") (pintype "bidirectional"))
      (node (ref "R103") (pin "1") (pinfunction "1_1") (pintype "passive"))
    )
    (net (code "56") (name "MISO2") (class "Default")
      (node (ref "M1C") (pin "33") (pinfunction "D16_33") (pintype "bidirectional"))
      (node (ref "R102") (pin "2") (pinfunction "2_2") (pintype "passive"))
    )
    (net (code "57") (name "MISO3") (class "Default")
      (node (ref "M1C") (pin "36") (pinfunction "E15_36") (pintype "bidirectional"))
      (node (ref "R112") (pin "2") (pinfunction "2_2") (pintype "passive"))
    )
    (net (code "58") (name "MISO4") (class "Default")
      (node (ref "M1C") (pin "35") (pinfunction "E16_35") (pintype "bidirectional"))
      (node (ref "R113") (pin "2") (pinfunction "2_2") (pintype "passive"))
    )
    (net (code "59") (name "MISO5") (class "Default")
      (node (ref "M1C") (pin "38") (pinfunction "F14_38") (pintype "bidirectional"))
      (node (ref "R111") (pin "2") (pinfunction "2_2") (pintype "passive"))
    )
    (net (code "60") (name "MISO6") (class "Default")
      (node (ref "M1C") (pin "37") (pinfunction "G15_37") (pintype "bidirectional"))
      (node (ref "R109") (pin "2") (pinfunction "2_2") (pintype "passive"))
    )
    (net (code "61") (name "MISO7") (class "Default")
      (node (ref "M1C") (pin "40") (pinfunction "G16_40") (pintype "bidirectional"))
      (node (ref "R110") (pin "2") (pinfunction "2_2") (pintype "passive"))
    )
    (net (code "62") (name "MISO8") (class "Default")
      (node (ref "M1C") (pin "39") (pinfunction "H14_39") (pintype "bidirectional"))
      (node (ref "R108") (pin "2") (pinfunction "2_2") (pintype "passive"))
    )
    (net (code "63") (name "MISO9") (class "Default")
      (node (ref "M1C") (pin "44") (pinfunction "H16_44") (pintype "bidirectional"))
      (node (ref "R107") (pin "2") (pinfunction "2_2") (pintype "passive"))
    )
    (net (code "64") (name "MISO10") (class "Default")
      (node (ref "M1C") (pin "43") (pinfunction "H13_43") (pintype "bidirectional"))
      (node (ref "R104") (pin "2") (pinfunction "2_2") (pintype "passive"))
    )
    (net (code "65") (name "MISO11") (class "Default")
      (node (ref "M1C") (pin "46") (pinfunction "G14_46") (pintype "bidirectional"))
      (node (ref "R106") (pin "2") (pinfunction "2_2") (pintype "passive"))
    )
    (net (code "66") (name "MISO12") (class "Default")
      (node (ref "M1C") (pin "45") (pinfunction "F15_45") (pintype "bidirectional"))
      (node (ref "R105") (pin "2") (pinfunction "2_2") (pintype "passive"))
    )
    (net (code "67") (name "MOSI") (class "Default")
      (node (ref "P1") (pin "1") (pinfunction "1_1") (pintype "bidirectional"))
      (node (ref "P10") (pin "1") (pinfunction "1_1") (pintype "bidirectional"))
      (node (ref "P11") (pin "1") (pinfunction "1_1") (pintype "bidirectional"))
      (node (ref "P12") (pin "1") (pinfunction "1_1") (pintype "bidirectional"))
      (node (ref "P2") (pin "1") (pinfunction "1_1") (pintype "bidirectional"))
      (node (ref "P3") (pin "1") (pinfunction "1_1") (pintype "bidirectional"))
      (node (ref "P4") (pin "1") (pinfunction "1_1") (pintype "bidirectional"))
      (node (ref "P5") (pin "1") (pinfunction "1_1") (pintype "bidirectional"))
      (node (ref "P6") (pin "1") (pinfunction "1_1") (pintype "bidirectional"))
      (node (ref "P7") (pin "1") (pinfunction "1_1") (pintype "bidirectional"))
      (node (ref "P8") (pin "1") (pinfunction "1_1") (pintype "bidirectional"))
      (node (ref "P9") (pin "1") (pinfunction "1_1") (pintype "bidirectional"))
      (node (ref "R100") (pin "2") (pinfunction "2_2") (pintype "passive"))
    )
    (net (code "68") (name "MOSIR") (class "Default")
      (node (ref "R100") (pin "1") (pinfunction "1_1") (pintype "passive"))
      (node (ref "U100") (pin "4") (pinfunction "2Y_4") (pintype "bidirectional"))
    )
    (net (code "69") (name "Net-(M1B-K3)") (class "Default")
      (node (ref "M1B") (pin "12") (pinfunction "K3_12") (pintype "bidirectional"))
      (node (ref "U105") (pin "3") (pinfunction "DS1_3") (pintype "passive"))
    )
    (net (code "70") (name "Net-(M1B-M1)") (class "Default")
      (node (ref "M1B") (pin "14") (pinfunction "M1_14") (pintype "bidirectional"))
      (node (ref "R115") (pin "1") (pinfunction "1_1") (pintype "passive"))
    )
    (net (code "71") (name "Net-(M1B-P3)") (class "Default")
      (node (ref "M1B") (pin "26") (pinfunction "P3_26") (pintype "bidirectional"))
      (node (ref "U106") (pin "1") (pinfunction "1A_1") (pintype "bidirectional"))
    )
    (net (code "72") (name "Net-(M1B-R3)") (class "Default")
      (node (ref "M1B") (pin "28") (pinfunction "R3_28") (pintype "bidirectional"))
      (node (ref "U106") (pin "3") (pinfunction "2A_3") (pintype "bidirectional"))
    )
    (net (code "73") (name "Net-(P2-Pad2)") (class "Default")
      (node (ref "P2") (pin "2") (pinfunction "2_2") (pintype "bidirectional"))
      (node (ref "R102") (pin "1") (pinfunction "1_1") (pintype "passive"))
    )
    (net (code "74") (name "Net-(P3-Pad2)") (class "Default")
      (node (ref "P3") (pin "2") (pinfunction "2_2") (pintype "bidirectional"))
      (node (ref "R112") (pin "1") (pinfunction "1_1") (pintype "passive"))
    )
    (net (code "75") (name "Net-(P4-Pad2)") (class "Default")
      (node (ref "P4") (pin "2") (pinfunction "2_2") (pintype "bidirectional"))
      (node (ref "R113") (pin "1") (pinfunction "1_1") (pintype "passive"))
    )
    (net (code "76") (name "Net-(P5-Pad2)") (class "Default")
      (node (ref "P5") (pin "2") (pinfunction "2_2") (pintype "bidirectional"))
      (node (ref "R111") (pin "1") (pinfunction "1_1") (pintype "passive"))
    )
    (net (code "77") (name "Net-(P6-Pad2)") (class "Default")
      (node (ref "P6") (pin "2") (pinfunction "2_2") (pintype "bidirectional"))
      (node (ref "R109") (pin "1") (pinfunction "1_1") (pintype "passive"))
    )
    (net (code "78") (name "Net-(P7-Pad2)") (class "Default")
      (node (ref "P7") (pin "2") (pinfunction "2_2") (pintype "bidirectional"))
      (node (ref "R110") (pin "1") (pinfunction "1_1") (pintype "passive"))
    )
    (net (code "79") (name "Net-(P8-Pad2)") (class "Default")
      (node (ref "P8") (pin "2") (pinfunction "2_2") (pintype "bidirectional"))
      (node (ref "R108") (pin "1") (pinfunction "1_1") (pintype "passive"))
    )
    (net (code "80") (name "Net-(P9-Pad2)") (class "Default")
      (node (ref "P9") (pin "2") (pinfunction "2_2") (pintype "bidirectional"))
      (node (ref "R107") (pin "1") (pinfunction "1_1") (pintype "passive"))
    )
    (net (code "81") (name "Net-(P10-Pad2)") (class "Default")
      (node (ref "P10") (pin "2") (pinfunction "2_2") (pintype "bidirectional"))
      (node (ref "R104") (pin "1") (pinfunction "1_1") (pintype "passive"))
    )
    (net (code "82") (name "Net-(P11-Pad2)") (class "Default")
      (node (ref "P11") (pin "2") (pinfunction "2_2") (pintype "bidirectional"))
      (node (ref "R106") (pin "1") (pinfunction "1_1") (pintype "passive"))
    )
    (net (code "83") (name "Net-(P12-Pad2)") (class "Default")
      (node (ref "P12") (pin "2") (pinfunction "2_2") (pintype "bidirectional"))
      (node (ref "R105") (pin "1") (pinfunction "1_1") (pintype "passive"))
    )
    (net (code "84") (name "Net-(U101-2Y)") (class "Default")
      (node (ref "JP100") (pin "1") (pinfunction "1_1") (pintype "passive"))
      (node (ref "U101") (pin "4") (pinfunction "2Y_4") (pintype "bidirectional"))
    )
    (net (code "85") (name "Net-(U103-NC{slash}FB)") (class "Default")
      (node (ref "C102") (pin "1") (pinfunction "1_1") (pintype "passive"))
      (node (ref "U103") (pin "4") (pinfunction "NC/FB_4") (pintype "passive"))
    )
    (net (code "86") (name "Net-(U104-+)") (class "Default")
      (node (ref "R119") (pin "1") (pinfunction "1_1") (pintype "passive"))
      (node (ref "R120") (pin "2") (pinfunction "2_2") (pintype "passive"))
      (node (ref "U104") (pin "3") (pinfunction "+_3") (pintype "bidirectional"))
    )
    (net (code "87") (name "Net-(U104--)") (class "Default")
      (node (ref "U104") (pin "4") (pinfunction "-_4") (pintype "bidirectional"))
      (node (ref "U104") (pin "5") (pinfunction "HY_5") (pintype "bidirectional"))
      (node (ref "U104") (pin "6") (pinfunction "1.182_6") (pintype "bidirectional"))
    )
    (net (code "88") (name "Net-(U104-OUT)") (class "Default")
      (node (ref "R117") (pin "1") (pinfunction "1_1") (pintype "passive"))
      (node (ref "U104") (pin "8") (pinfunction "OUT_8") (pintype "bidirectional"))
    )
    (net (code "89") (name "Net-(U105-A)") (class "Default")
      (node (ref "R117") (pin "2") (pinfunction "2_2") (pintype "passive"))
      (node (ref "U105") (pin "1") (pinfunction "A_1") (pintype "passive"))
    )
    (net (code "90") (name "Net-(U106-1Y)") (class "Default")
      (node (ref "R116") (pin "1") (pinfunction "1_1") (pintype "passive"))
      (node (ref "U106") (pin "6") (pinfunction "1Y_6") (pintype "bidirectional"))
    )
    (net (code "91") (name "Net-(U106-2Y)") (class "Default")
      (node (ref "R118") (pin "1") (pinfunction "1_1") (pintype "passive"))
      (node (ref "U106") (pin "4") (pinfunction "2Y_4") (pintype "bidirectional"))
    )
    (net (code "92") (name "Net-(U108-A)") (class "Default")
      (node (ref "R115") (pin "2") (pinfunction "2_2") (pintype "passive"))
      (node (ref "U108") (pin "1") (pinfunction "A_1") (pintype "passive"))
    )
    (net (code "93") (name "Net-(U109-1Y)") (class "Default")
      (node (ref "R121") (pin "2") (pinfunction "2_2") (pintype "passive"))
      (node (ref "U109") (pin "6") (pinfunction "1Y_6") (pintype "bidirectional"))
    )
    (net (code "94") (name "Net-(U109-2Y)") (class "Default")
      (node (ref "R122") (pin "2") (pinfunction "2_2") (pintype "passive"))
      (node (ref "U109") (pin "4") (pinfunction "2Y_4") (pintype "bidirectional"))
    )
    (net (code "95") (name "OE#") (class "Default")
      (node (ref "M1B") (pin "4") (pinfunction "P10_4") (pintype "bidirectional"))
      (node (ref "U102") (pin "28") (pinfunction "~{OE}_28") (pintype "bidirectional"))
    )
    (net (code "96") (name "SPARE") (class "Default")
      (node (ref "M1B") (pin "9") (pinfunction "+3V3_3_9") (pintype "bidirectional"))
      (node (ref "U101") (pin "3") (pinfunction "2A_3") (pintype "bidirectional"))
    )
    (net (code "97") (name "SYNC") (class "Default")
      (node (ref "J101") (pin "S") (pinfunction "1_S") (pintype "passive"))
      (node (ref "R118") (pin "2") (pinfunction "2_2") (pintype "passive"))
    )
    (net (code "98") (name "SYNC_INV") (class "Default")
      (node (ref "JP103") (pin "1") (pinfunction "1_1") (pintype "passive"))
      (node (ref "M1B") (pin "23") (pinfunction "P1_23") (pintype "bidirectional"))
      (node (ref "R125") (pin "2") (pinfunction "2_2") (pintype "passive"))
    )
    (net (code "99") (name "TEN") (class "Default")
      (node (ref "M1B") (pin "7") (pinfunction "K2_7") (pintype "bidirectional"))
      (node (ref "P1") (pin "7") (pinfunction "7_7") (pintype "bidirectional"))
      (node (ref "P10") (pin "7") (pinfunction "7_7") (pintype "bidirectional"))
      (node (ref "P11") (pin "7") (pinfunction "7_7") (pintype "bidirectional"))
      (node (ref "P12") (pin "7") (pinfunction "7_7") (pintype "bidirectional"))
      (node (ref "P2") (pin "7") (pinfunction "7_7") (pintype "bidirectional"))
      (node (ref "P3") (pin "7") (pinfunction "7_7") (pintype "bidirectional"))
      (node (ref "P4") (pin "7") (pinfunction "7_7") (pintype "bidirectional"))
      (node (ref "P5") (pin "7") (pinfunction "7_7") (pintype "bidirectional"))
      (node (ref "P6") (pin "7") (pinfunction "7_7") (pintype "bidirectional"))
      (node (ref "P7") (pin "7") (pinfunction "7_7") (pintype "bidirectional"))
      (node (ref "P8") (pin "7") (pinfunction "7_7") (pintype "bidirectional"))
      (node (ref "P9") (pin "7") (pinfunction "7_7") (pintype "bidirectional"))
    )
    (net (code "100") (name "TMI1") (class "Default")
      (node (ref "M1B") (pin "8") (pinfunction "K1_8") (pintype "bidirectional"))
      (node (ref "P1") (pin "5") (pinfunction "5_5") (pintype "bidirectional"))
    )
    (net (code "101") (name "TMO1") (class "Default")
      (node (ref "P1") (pin "6") (pinfunction "6_6") (pintype "bidirectional"))
      (node (ref "P2") (pin "5") (pinfunction "5_5") (pintype "bidirectional"))
    )
    (net (code "102") (name "TMO2") (class "Default")
      (node (ref "P2") (pin "6") (pinfunction "6_6") (pintype "bidirectional"))
      (node (ref "P3") (pin "5") (pinfunction "5_5") (pintype "bidirectional"))
    )
    (net (code "103") (name "TMO3") (class "Default")
      (node (ref "P3") (pin "6") (pinfunction "6_6") (pintype "bidirectional"))
      (node (ref "P4") (pin "5") (pinfunction "5_5") (pintype "bidirectional"))
    )
    (net (code "104") (name "TMO4") (class "Default")
      (node (ref "P4") (pin "6") (pinfunction "6_6") (pintype "bidirectional"))
      (node (ref "P5") (pin "5") (pinfunction "5_5") (pintype "bidirectional"))
    )
    (net (code "105") (name "TMO5") (class "Default")
      (node (ref "P5") (pin "6") (pinfunction "6_6") (pintype "bidirectional"))
      (node (ref "P6") (pin "5") (pinfunction "5_5") (pintype "bidirectional"))
    )
    (net (code "106") (name "TMO6") (class "Default")
      (node (ref "P6") (pin "6") (pinfunction "6_6") (pintype "bidirectional"))
      (node (ref "P7") (pin "5") (pinfunction "5_5") (pintype "bidirectional"))
    )
    (net (code "107") (name "TMO7") (class "Default")
      (node (ref "P7") (pin "6") (pinfunction "6_6") (pintype "bidirectional"))
      (node (ref "P8") (pin "5") (pinfunction "5_5") (pintype "bidirectional"))
    )
    (net (code "108") (name "TMO8") (class "Default")
      (node (ref "P8") (pin "6") (pinfunction "6_6") (pintype "bidirectional"))
      (node (ref "P9") (pin "5") (pinfunction "5_5") (pintype "bidirectional"))
    )
    (net (code "109") (name "TMO9") (class "Default")
      (node (ref "P10") (pin "5") (pinfunction "5_5") (pintype "bidirectional"))
      (node (ref "P9") (pin "6") (pinfunction "6_6") (pintype "bidirectional"))
    )
    (net (code "110") (name "TMO10") (class "Default")
      (node (ref "P10") (pin "6") (pinfunction "6_6") (pintype "bidirectional"))
      (node (ref "P11") (pin "5") (pinfunction "5_5") (pintype "bidirectional"))
    )
    (net (code "111") (name "TMO11") (class "Default")
      (node (ref "P11") (pin "6") (pinfunction "6_6") (pintype "bidirectional"))
      (node (ref "P12") (pin "5") (pinfunction "5_5") (pintype "bidirectional"))
    )
    (net (code "112") (name "TMO12") (class "Default")
      (node (ref "M1C") (pin "47") (pinfunction "E12_47") (pintype "bidirectional"))
      (node (ref "P12") (pin "6") (pinfunction "6_6") (pintype "bidirectional"))
    )
    (net (code "113") (name "TP0") (class "Default")
      (node (ref "M1B") (pin "48") (pinfunction "T10_48") (pintype "bidirectional"))
    )
    (net (code "114") (name "TP1") (class "Default")
      (node (ref "M1B") (pin "47") (pinfunction "T8_47") (pintype "bidirectional"))
    )
    (net (code "115") (name "TP2") (class "Default")
      (node (ref "M1B") (pin "46") (pinfunction "R8_46") (pintype "bidirectional"))
    )
    (net (code "116") (name "TP3") (class "Default")
      (node (ref "M1B") (pin "45") (pinfunction "T7_45") (pintype "bidirectional"))
    )
    (net (code "117") (name "TP4") (class "Default")
      (node (ref "M1B") (pin "44") (pinfunction "R7_44") (pintype "bidirectional"))
    )
    (net (code "118") (name "TP5") (class "Default")
      (node (ref "M1B") (pin "43") (pinfunction "T9_43") (pintype "bidirectional"))
    )
    (net (code "119") (name "TP6") (class "Default")
      (node (ref "M1B") (pin "40") (pinfunction "R6_40") (pintype "bidirectional"))
    )
    (net (code "120") (name "TP7") (class "Default")
      (node (ref "M1B") (pin "39") (pinfunction "T5_39") (pintype "bidirectional"))
    )
    (net (code "121") (name "TP8") (class "Default")
      (node (ref "M1B") (pin "38") (pinfunction "P8_38") (pintype "bidirectional"))
    )
    (net (code "122") (name "TP9") (class "Default")
      (node (ref "M1B") (pin "37") (pinfunction "R5_37") (pintype "bidirectional"))
    )
    (net (code "123") (name "TP10") (class "Default")
      (node (ref "M1B") (pin "36") (pinfunction "N6_36") (pintype "bidirectional"))
    )
    (net (code "124") (name "TP11") (class "Default")
      (node (ref "M1B") (pin "35") (pinfunction "P5_35") (pintype "bidirectional"))
    )
    (net (code "125") (name "TP12") (class "Default")
      (node (ref "M1B") (pin "34") (pinfunction "T4_34") (pintype "bidirectional"))
    )
    (net (code "126") (name "TP13") (class "Default")
      (node (ref "M1B") (pin "33") (pinfunction "P4_33") (pintype "bidirectional"))
    )
    (net (code "127") (name "TP14") (class "Default")
      (node (ref "M1B") (pin "30") (pinfunction "N4_30") (pintype "bidirectional"))
    )
    (net (code "128") (name "TP15") (class "Default")
      (node (ref "M1B") (pin "29") (pinfunction "T3_29") (pintype "bidirectional"))
    )
    (net (code "129") (name "UCLK") (class "Default")
      (node (ref "M1C") (pin "27") (pinfunction "B15_27") (pintype "bidirectional"))
      (node (ref "U101") (pin "1") (pinfunction "1A_1") (pintype "bidirectional"))
    )
    (net (code "130") (name "UCS") (class "Default")
      (node (ref "M1C") (pin "30") (pinfunction "D15_30") (pintype "bidirectional"))
      (node (ref "U100") (pin "1") (pinfunction "1A_1") (pintype "bidirectional"))
    )
    (net (code "131") (name "ULED1") (class "Default")
      (node (ref "M1B") (pin "11") (pinfunction "L2_11") (pintype "bidirectional"))
      (node (ref "U109") (pin "3") (pinfunction "2A_3") (pintype "bidirectional"))
    )
    (net (code "132") (name "ULED2") (class "Default")
      (node (ref "M1B") (pin "13") (pinfunction "L3_13") (pintype "bidirectional"))
      (node (ref "U109") (pin "1") (pinfunction "1A_1") (pintype "bidirectional"))
    )
    (net (code "133") (name "UMOSI") (class "Default")
      (node (ref "M1C") (pin "29") (pinfunction "C16_29") (pintype "bidirectional"))
      (node (ref "U100") (pin "3") (pinfunction "2A_3") (pintype "bidirectional"))
    )
    (net (code "134") (name "VIN") (class "Default")
      (node (ref "C109") (pin "1") (pinfunction "1_1") (pintype "passive"))
      (node (ref "C110") (pin "1") (pinfunction "1_1") (pintype "passive"))
      (node (ref "J105") (pin "1A") (pinfunction "P$1_1A") (pintype "bidirectional"))
      (node (ref "J105") (pin "1B") (pinfunction "P$1_1B") (pintype "bidirectional"))
      (node (ref "U107") (pin "1") (pinfunction "IN_1") (pintype "input"))
    )
    (net (code "135") (name "WE#") (class "Default")
      (node (ref "M1C") (pin "13") (pinfunction "B10_13") (pintype "bidirectional"))
      (node (ref "U102") (pin "11") (pinfunction "~{WE}_11") (pintype "bidirectional"))
    )
    (net (code "136") (name "unconnected-(J104-P$2-Pad2)") (class "Default")
      (node (ref "J104") (pin "2") (pinfunction "P$2_2") (pintype "bidirectional"))
    )
    (net (code "137") (name "unconnected-(J105-P$2-Pad3)") (class "Default")
      (node (ref "J105") (pin "3") (pinfunction "P$2_3") (pintype "bidirectional"))
    )
    (net (code "138") (name "unconnected-(M1B-+3V3_4-Pad10)") (class "Default")
      (node (ref "M1B") (pin "10") (pinfunction "+3V3_4_10") (pintype "bidirectional"))
    )
    (net (code "139") (name "unconnected-(M1B-CLK5-Pad3)") (class "Default")
      (node (ref "M1B") (pin "3") (pinfunction "CLK5_3") (pintype "bidirectional"))
    )
    (net (code "140") (name "unconnected-(M1B-L4-Pad16)") (class "Default")
      (node (ref "M1B") (pin "16") (pinfunction "L4_16") (pintype "bidirectional"))
    )
    (net (code "141") (name "unconnected-(M1B-M2-Pad15)") (class "Default")
      (node (ref "M1B") (pin "15") (pinfunction "M2_15") (pintype "bidirectional"))
    )
    (net (code "142") (name "unconnected-(M1B-M4-Pad17)") (class "Default")
      (node (ref "M1B") (pin "17") (pinfunction "M4_17") (pintype "bidirectional"))
    )
    (net (code "143") (name "unconnected-(M1B-N1-Pad18)") (class "Default")
      (node (ref "M1B") (pin "18") (pinfunction "N1_18") (pintype "bidirectional"))
    )
    (net (code "144") (name "unconnected-(M1B-N3-Pad22)") (class "Default")
      (node (ref "M1B") (pin "22") (pinfunction "N3_22") (pintype "bidirectional"))
    )
    (net (code "145") (name "unconnected-(M1B-R1-Pad24)") (class "Default")
      (node (ref "M1B") (pin "24") (pinfunction "R1_24") (pintype "bidirectional"))
    )
    (net (code "146") (name "unconnected-(M1C-+3V3_7-Pad9)") (class "Default")
      (node (ref "M1C") (pin "9") (pinfunction "+3V3_7_9") (pintype "bidirectional"))
    )
    (net (code "147") (name "unconnected-(M1C-+3V3_8-Pad10)") (class "Default")
      (node (ref "M1C") (pin "10") (pinfunction "+3V3_8_10") (pintype "bidirectional"))
    )
    (net (code "148") (name "unconnected-(M1C-+3V3_9-Pad41)") (class "Default")
      (node (ref "M1C") (pin "41") (pinfunction "+3V3_9_41") (pintype "bidirectional"))
    )
    (net (code "149") (name "unconnected-(M1C-+3V3_10-Pad42)") (class "Default")
      (node (ref "M1C") (pin "42") (pinfunction "+3V3_10_42") (pintype "bidirectional"))
    )
    (net (code "150") (name "unconnected-(M1C-CLK4-Pad48)") (class "Default")
      (node (ref "M1C") (pin "48") (pinfunction "CLK4_48") (pintype "bidirectional"))
    )
    (net (code "151") (name "unconnected-(P1-Pad8)") (class "Default")
      (node (ref "P1") (pin "8") (pinfunction "8_8") (pintype "bidirectional"))
    )
    (net (code "152") (name "unconnected-(P2-Pad8)") (class "Default")
      (node (ref "P2") (pin "8") (pinfunction "8_8") (pintype "bidirectional"))
    )
    (net (code "153") (name "unconnected-(P3-Pad8)") (class "Default")
      (node (ref "P3") (pin "8") (pinfunction "8_8") (pintype "bidirectional"))
    )
    (net (code "154") (name "unconnected-(P4-Pad8)") (class "Default")
      (node (ref "P4") (pin "8") (pinfunction "8_8") (pintype "bidirectional"))
    )
    (net (code "155") (name "unconnected-(P5-Pad8)") (class "Default")
      (node (ref "P5") (pin "8") (pinfunction "8_8") (pintype "bidirectional"))
    )
    (net (code "156") (name "unconnected-(P6-Pad8)") (class "Default")
      (node (ref "P6") (pin "8") (pinfunction "8_8") (pintype "bidirectional"))
    )
    (net (code "157") (name "unconnected-(P7-Pad8)") (class "Default")
      (node (ref "P7") (pin "8") (pinfunction "8_8") (pintype "bidirectional"))
    )
    (net (code "158") (name "unconnected-(P8-Pad8)") (class "Default")
      (node (ref "P8") (pin "8") (pinfunction "8_8") (pintype "bidirectional"))
    )
    (net (code "159") (name "unconnected-(P9-Pad8)") (class "Default")
      (node (ref "P9") (pin "8") (pinfunction "8_8") (pintype "bidirectional"))
    )
    (net (code "160") (name "unconnected-(P10-Pad8)") (class "Default")
      (node (ref "P10") (pin "8") (pinfunction "8_8") (pintype "bidirectional"))
    )
    (net (code "161") (name "unconnected-(P11-Pad8)") (class "Default")
      (node (ref "P11") (pin "8") (pinfunction "8_8") (pintype "bidirectional"))
    )
    (net (code "162") (name "unconnected-(P12-Pad8)") (class "Default")
      (node (ref "P12") (pin "8") (pinfunction "8_8") (pintype "bidirectional"))
    )
    (net (code "163") (name "~{CSR}") (class "Default")
      (node (ref "R101") (pin "1") (pinfunction "1_1") (pintype "passive"))
      (node (ref "U100") (pin "6") (pinfunction "1Y_6") (pintype "bidirectional"))
    )
    (net (code "164") (name "~{CS}") (class "Default")
      (node (ref "P1") (pin "4") (pinfunction "4_4") (pintype "bidirectional"))
      (node (ref "P10") (pin "4") (pinfunction "4_4") (pintype "bidirectional"))
      (node (ref "P11") (pin "4") (pinfunction "4_4") (pintype "bidirectional"))
      (node (ref "P12") (pin "4") (pinfunction "4_4") (pintype "bidirectional"))
      (node (ref "P2") (pin "4") (pinfunction "4_4") (pintype "bidirectional"))
      (node (ref "P3") (pin "4") (pinfunction "4_4") (pintype "bidirectional"))
      (node (ref "P4") (pin "4") (pinfunction "4_4") (pintype "bidirectional"))
      (node (ref "P5") (pin "4") (pinfunction "4_4") (pintype "bidirectional"))
      (node (ref "P6") (pin "4") (pinfunction "4_4") (pintype "bidirectional"))
      (node (ref "P7") (pin "4") (pinfunction "4_4") (pintype "bidirectional"))
      (node (ref "P8") (pin "4") (pinfunction "4_4") (pintype "bidirectional"))
      (node (ref "P9") (pin "4") (pinfunction "4_4") (pintype "bidirectional"))
      (node (ref "R101") (pin "2") (pinfunction "2_2") (pintype "passive"))
    )
  )
)
